# FotoMindARShield.net
KiCad netlist of a schematic drawn in EAGLE
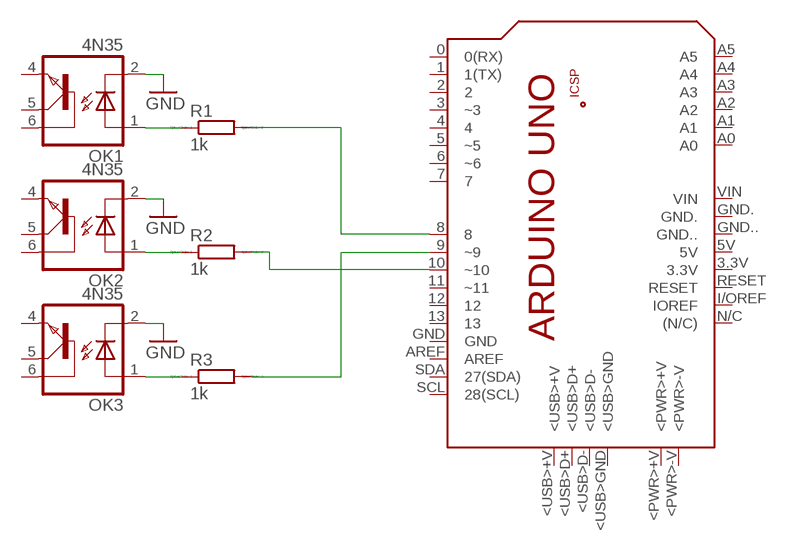
[diagram p0: schematic, sheet 1]

(export (version "E")
  (design (tool "Eeschema 10.0.6"))
  (components
    (comp (ref "OK1")
      (value "4N35")
      (footprint "eagle-import:DIL06")
      (fields (field (name "MF") "FAIRCHILD SEMICONDUCTOR"))
      (libsource (lib "eagle-import") (part "4N35"))
    )
    (comp (ref "OK2")
      (value "4N35")
      (footprint "eagle-import:DIL06")
      (fields (field (name "MF") "FAIRCHILD SEMICONDUCTOR"))
      (libsource (lib "eagle-import") (part "4N35"))
    )
    (comp (ref "OK3")
      (value "4N35")
      (footprint "eagle-import:DIL06")
      (fields (field (name "MF") "FAIRCHILD SEMICONDUCTOR"))
      (libsource (lib "eagle-import") (part "4N35"))
    )
    (comp (ref "PCB1")
      (value "ARDUINO_UNO")
      (footprint "eagle-import:ARDUINO_UNO")
      (libsource (lib "eagle-import") (part "ARDUINO_UNO"))
    )
    (comp (ref "R1")
      (value "1k")
      (footprint "eagle-import:0204_7")
      (libsource (lib "eagle-import") (part "R0204/7"))
    )
    (comp (ref "R2")
      (value "1k")
      (footprint "eagle-import:0204_7")
      (libsource (lib "eagle-import") (part "R0204/7"))
    )
    (comp (ref "R3")
      (value "1k")
      (footprint "eagle-import:0204_7")
      (libsource (lib "eagle-import") (part "R0204/7"))
    )
  )
  (nets
    (net (code "1") (name "GND") (class "Default")
      (node (ref "OK1") (pin "2") (pinfunction "C_2") (pintype "passive"))
      (node (ref "OK2") (pin "2") (pinfunction "C_2") (pintype "passive"))
      (node (ref "OK3") (pin "2") (pinfunction "C_2") (pintype "passive"))
    )
    (net (code "2") (name "Net-(OK1-A)") (class "Default")
      (node (ref "OK1") (pin "1") (pinfunction "A_1") (pintype "passive"))
      (node (ref "R1") (pin "1") (pinfunction "1_1") (pintype "passive"))
    )
    (net (code "3") (name "Net-(OK2-A)") (class "Default")
      (node (ref "OK2") (pin "1") (pinfunction "A_1") (pintype "passive"))
      (node (ref "R2") (pin "1") (pinfunction "1_1") (pintype "passive"))
    )
    (net (code "4") (name "Net-(OK3-A)") (class "Default")
      (node (ref "OK3") (pin "1") (pinfunction "A_1") (pintype "passive"))
      (node (ref "R3") (pin "1") (pinfunction "1_1") (pintype "passive"))
    )
    (net (code "5") (name "Net-(PCB1-Pad8)") (class "Default")
      (node (ref "PCB1") (pin "8") (pinfunction "8_8") (pintype "bidirectional"))
      (node (ref "R1") (pin "2") (pinfunction "2_2") (pintype "passive"))
    )
    (net (code "6") (name "Net-(PCB1-~{9})") (class "Default")
      (node (ref "PCB1") (pin "9") (pinfunction "~{9}_9") (pintype "bidirectional"))
      (node (ref "R3") (pin "2") (pinfunction "2_2") (pintype "passive"))
    )
    (net (code "7") (name "Net-(PCB1-~{10})") (class "Default")
      (node (ref "PCB1") (pin "10") (pinfunction "~{10}_10") (pintype "bidirectional"))
      (node (ref "R2") (pin "2") (pinfunction "2_2") (pintype "passive"))
    )
    (net (code "8") (name "unconnected-(OK1-BAS-Pad6)") (class "Default")
      (node (ref "OK1") (pin "6") (pinfunction "BAS_6") (pintype "passive"))
    )
    (net (code "9") (name "unconnected-(OK1-COL-Pad5)") (class "Default")
      (node (ref "OK1") (pin "5") (pinfunction "COL_5") (pintype "passive"))
    )
    (net (code "10") (name "unconnected-(OK1-EMI-Pad4)") (class "Default")
      (node (ref "OK1") (pin "4") (pinfunction "EMI_4") (pintype "passive"))
    )
    (net (code "11") (name "unconnected-(OK2-BAS-Pad6)") (class "Default")
      (node (ref "OK2") (pin "6") (pinfunction "BAS_6") (pintype "passive"))
    )
    (net (code "12") (name "unconnected-(OK2-COL-Pad5)") (class "Default")
      (node (ref "OK2") (pin "5") (pinfunction "COL_5") (pintype "passive"))
    )
    (net (code "13") (name "unconnected-(OK2-EMI-Pad4)") (class "Default")
      (node (ref "OK2") (pin "4") (pinfunction "EMI_4") (pintype "passive"))
    )
    (net (code "14") (name "unconnected-(OK3-BAS-Pad6)") (class "Default")
      (node (ref "OK3") (pin "6") (pinfunction "BAS_6") (pintype "passive"))
    )
    (net (code "15") (name "unconnected-(OK3-COL-Pad5)") (class "Default")
      (node (ref "OK3") (pin "5") (pinfunction "COL_5") (pintype "passive"))
    )
    (net (code "16") (name "unconnected-(OK3-EMI-Pad4)") (class "Default")
      (node (ref "OK3") (pin "4") (pinfunction "EMI_4") (pintype "passive"))
    )
    (net (code "17") (name "unconnected-(PCB1-(N{slash}C)-PadN{slash}C)") (class "Default")
      (node (ref "PCB1") (pin "N/C") (pinfunction "(N/C)_N/C") (pintype "bidirectional"))
    )
    (net (code "18") (name "unconnected-(PCB1-0(RX)-Pad0)") (class "Default")
      (node (ref "PCB1") (pin "0") (pinfunction "0(RX)_0") (pintype "bidirectional"))
    )
    (net (code "19") (name "unconnected-(PCB1-1(TX)-Pad1)") (class "Default")
      (node (ref "PCB1") (pin "1") (pinfunction "1(TX)_1") (pintype "bidirectional"))
    )
    (net (code "20") (name "unconnected-(PCB1-27(SDA)-PadSDA)") (class "Default")
      (node (ref "PCB1") (pin "SDA") (pinfunction "27(SDA)_SDA") (pintype "bidirectional"))
    )
    (net (code "21") (name "unconnected-(PCB1-28(SCL)-PadSCL)") (class "Default")
      (node (ref "PCB1") (pin "SCL") (pinfunction "28(SCL)_SCL") (pintype "bidirectional"))
    )
    (net (code "22") (name "unconnected-(PCB1-IOREF-PadI{slash}OREF)") (class "Default")
      (node (ref "PCB1") (pin "I/OREF") (pinfunction "IOREF_I/OREF") (pintype "bidirectional"))
    )
    (net (code "23") (name "unconnected-(PCB1-Pad+5V)") (class "Default")
      (node (ref "PCB1") (pin "+5V") (pinfunction "+5V_+5V") (pintype "bidirectional"))
    )
    (net (code "24") (name "unconnected-(PCB1-Pad2)") (class "Default")
      (node (ref "PCB1") (pin "2") (pinfunction "2_2") (pintype "bidirectional"))
    )
    (net (code "25") (name "unconnected-(PCB1-Pad3.3V)") (class "Default")
      (node (ref "PCB1") (pin "3.3V") (pinfunction "3.3V_3.3V") (pintype "bidirectional"))
    )
    (net (code "26") (name "unconnected-(PCB1-Pad4)") (class "Default")
      (node (ref "PCB1") (pin "4") (pinfunction "4_4") (pintype "bidirectional"))
    )
    (net (code "27") (name "unconnected-(PCB1-Pad5V)") (class "Default")
      (node (ref "PCB1") (pin "5V") (pinfunction "5V_5V") (pintype "bidirectional"))
    )
    (net (code "28") (name "unconnected-(PCB1-Pad7)") (class "Default")
      (node (ref "PCB1") (pin "7") (pinfunction "7_7") (pintype "bidirectional"))
    )
    (net (code "29") (name "unconnected-(PCB1-Pad12)") (class "Default")
      (node (ref "PCB1") (pin "12") (pinfunction "12_12") (pintype "bidirectional"))
    )
    (net (code "30") (name "unconnected-(PCB1-Pad13)") (class "Default")
      (node (ref "PCB1") (pin "13") (pinfunction "13_13") (pintype "bidirectional"))
    )
    (net (code "31") (name "unconnected-(PCB1-Pad<PWR>+V)") (class "Default")
      (node (ref "PCB1") (pin "<PWR>+V") (pinfunction "<PWR>+V_<PWR>+V") (pintype "bidirectional"))
    )
    (net (code "32") (name "unconnected-(PCB1-Pad<PWR>-V)") (class "Default")
      (node (ref "PCB1") (pin "<PWR>-V") (pinfunction "<PWR>-V_<PWR>-V") (pintype "bidirectional"))
    )
    (net (code "33") (name "unconnected-(PCB1-Pad<USB>+V)") (class "Default")
      (node (ref "PCB1") (pin "<USB>+V") (pinfunction "<USB>+V_<USB>+V") (pintype "bidirectional"))
    )
    (net (code "34") (name "unconnected-(PCB1-Pad<USB>D+)") (class "Default")
      (node (ref "PCB1") (pin "<USB>D+") (pinfunction "<USB>D+_<USB>D+") (pintype "bidirectional"))
    )
    (net (code "35") (name "unconnected-(PCB1-Pad<USB>D-)") (class "Default")
      (node (ref "PCB1") (pin "<USB>D-") (pinfunction "<USB>D-_<USB>D-") (pintype "bidirectional"))
    )
    (net (code "36") (name "unconnected-(PCB1-Pad<USB>GND)") (class "Default")
      (node (ref "PCB1") (pin "<USB>GND") (pinfunction "<USB>GND_<USB>GND") (pintype "bidirectional"))
    )
    (net (code "37") (name "unconnected-(PCB1-PadA0)") (class "Default")
      (node (ref "PCB1") (pin "A0") (pinfunction "A0_A0") (pintype "bidirectional"))
    )
    (net (code "38") (name "unconnected-(PCB1-PadA1)") (class "Default")
      (node (ref "PCB1") (pin "A1") (pinfunction "A1_A1") (pintype "bidirectional"))
    )
    (net (code "39") (name "unconnected-(PCB1-PadA2)") (class "Default")
      (node (ref "PCB1") (pin "A2") (pinfunction "A2_A2") (pintype "bidirectional"))
    )
    (net (code "40") (name "unconnected-(PCB1-PadA3)") (class "Default")
      (node (ref "PCB1") (pin "A3") (pinfunction "A3_A3") (pintype "bidirectional"))
    )
    (net (code "41") (name "unconnected-(PCB1-PadA4)") (class "Default")
      (node (ref "PCB1") (pin "A4") (pinfunction "A4_A4") (pintype "bidirectional"))
    )
    (net (code "42") (name "unconnected-(PCB1-PadA5)") (class "Default")
      (node (ref "PCB1") (pin "A5") (pinfunction "A5_A5") (pintype "bidirectional"))
    )
    (net (code "43") (name "unconnected-(PCB1-PadAREF)") (class "Default")
      (node (ref "PCB1") (pin "AREF") (pinfunction "AREF_AREF") (pintype "bidirectional"))
    )
    (net (code "44") (name "unconnected-(PCB1-PadGND)") (class "Default")
      (node (ref "PCB1") (pin "GND") (pinfunction "GND_GND") (pintype "bidirectional"))
    )
    (net (code "45") (name "unconnected-(PCB1-PadGND.)") (class "Default")
      (node (ref "PCB1") (pin "GND.") (pinfunction "GND._GND.") (pintype "bidirectional"))
    )
    (net (code "46") (name "unconnected-(PCB1-PadGND..)") (class "Default")
      (node (ref "PCB1") (pin "GND..") (pinfunction "GND.._GND..") (pintype "bidirectional"))
    )
    (net (code "47") (name "unconnected-(PCB1-PadGND_)") (class "Default")
      (node (ref "PCB1") (pin "GND_") (pinfunction "GND__GND_") (pintype "bidirectional"))
    )
    (net (code "48") (name "unconnected-(PCB1-PadMISO)") (class "Default")
      (node (ref "PCB1") (pin "MISO") (pinfunction "MISO_MISO") (pintype "bidirectional"))
    )
    (net (code "49") (name "unconnected-(PCB1-PadMOSI)") (class "Default")
      (node (ref "PCB1") (pin "MOSI") (pinfunction "MOSI_MOSI") (pintype "bidirectional"))
    )
    (net (code "50") (name "unconnected-(PCB1-PadRESET)") (class "Default")
      (node (ref "PCB1") (pin "RESET") (pinfunction "RESET_RESET") (pintype "bidirectional"))
    )
    (net (code "51") (name "unconnected-(PCB1-PadRESET.)") (class "Default")
      (node (ref "PCB1") (pin "RESET.") (pinfunction "RESET._RESET.") (pintype "bidirectional"))
    )
    (net (code "52") (name "unconnected-(PCB1-PadSCK)") (class "Default")
      (node (ref "PCB1") (pin "SCK") (pinfunction "SCK_SCK") (pintype "bidirectional"))
    )
    (net (code "53") (name "unconnected-(PCB1-PadVIN)") (class "Default")
      (node (ref "PCB1") (pin "VIN") (pinfunction "VIN_VIN") (pintype "bidirectional"))
    )
    (net (code "54") (name "unconnected-(PCB1-~{3}-Pad3)") (class "Default")
      (node (ref "PCB1") (pin "3") (pinfunction "~{3}_3") (pintype "bidirectional"))
    )
    (net (code "55") (name "unconnected-(PCB1-~{5}-Pad5)") (class "Default")
      (node (ref "PCB1") (pin "5") (pinfunction "~{5}_5") (pintype "bidirectional"))
    )
    (net (code "56") (name "unconnected-(PCB1-~{6}-Pad6)") (class "Default")
      (node (ref "PCB1") (pin "6") (pinfunction "~{6}_6") (pintype "bidirectional"))
    )
    (net (code "57") (name "unconnected-(PCB1-~{11}-Pad11)") (class "Default")
      (node (ref "PCB1") (pin "11") (pinfunction "~{11}_11") (pintype "bidirectional"))
    )
  )
)
